# Power.net
KiCad netlist of a schematic drawn in Altium Designer
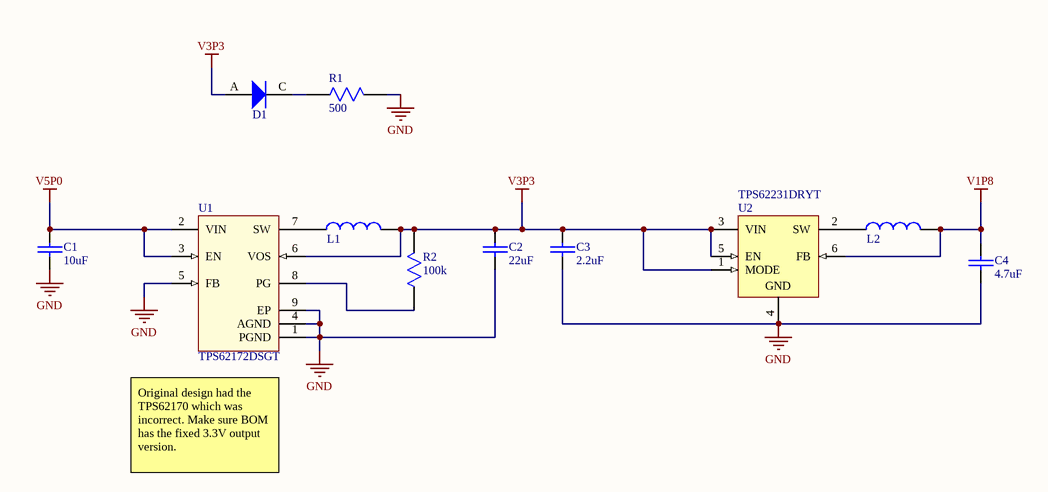
[diagram p0: Power.SchDoc]

(export (version "E")
  (design (tool "Eeschema 10.0.6"))
  (components
    (comp (ref "C1")
      (value "10uF")
      (footprint "SMD Capacitor 0603")
      (libsource (lib "DA_Component_Library") (part "Capacitor"))
    )
    (comp (ref "C2")
      (value "22uF")
      (footprint "SMD Capacitor 0603")
      (libsource (lib "DA_Component_Library") (part "Capacitor"))
    )
    (comp (ref "C3")
      (value "2.2uF")
      (footprint "SMD CAP 0402")
      (libsource (lib "DA_Component_Library") (part "Capacitor"))
    )
    (comp (ref "C4")
      (value "4.7uF")
      (footprint "SMD CAP 0402")
      (libsource (lib "DA_Component_Library") (part "Capacitor"))
    )
    (comp (ref "D1")
      (value "LED 0603")
      (footprint "LED_0603")
      (description "LTST_C195TBJRKT")
      (libsource (lib "DA_Component_Library") (part "LED 0603"))
    )
    (comp (ref "L1")
      (value "Ferrite Bead")
      (footprint "LQM21PN2R2MC0D")
      (libsource (lib "DA_Component_Library") (part "Ferrite Bead"))
    )
    (comp (ref "L2")
      (value "Ferrite Bead")
      (footprint "LQM21PN2R2MC0D")
      (libsource (lib "DA_Component_Library") (part "Ferrite Bead"))
    )
    (comp (ref "R1")
      (value "500")
      (footprint "SMD RES 0402")
      (libsource (lib "DA_Component_Library") (part "Resistor"))
    )
    (comp (ref "R2")
      (value "100k")
      (footprint "SMD RES 0402")
      (libsource (lib "DA_Component_Library") (part "Resistor"))
    )
    (comp (ref "U1")
      (value "TPS62172DSGT")
      (footprint "DSG8-1600X900TP")
      (fields (field (name "MANUFACTURER") "Texas Instruments") (field (name "PARTNUMBER") "TPS62170DSGT"))
      (libsource (lib "TI Power Management Step-Down Regulator") (part "TPS62170DSGT"))
    )
    (comp (ref "U2")
      (value "TPS62231DRYT")
      (footprint "DRY6")
      (fields (field (name "MANUFACTURER") "Texas Instruments"))
      (libsource (lib "TI Power Management Step-Down Regulator") (part "TPS62231DRYT"))
    )
  )
  (nets
    (net (code "1") (name "GND") (class "Default")
      (node (ref "C1") (pin "1") (pinfunction "1_1") (pintype "passive"))
      (node (ref "C2") (pin "1") (pinfunction "1_1") (pintype "passive"))
      (node (ref "C3") (pin "1") (pinfunction "1_1") (pintype "passive"))
      (node (ref "C4") (pin "1") (pinfunction "1_1") (pintype "passive"))
      (node (ref "R1") (pin "1") (pinfunction "1_1") (pintype "passive"))
      (node (ref "U1") (pin "1") (pinfunction "PGND_1") (pintype "power_in"))
      (node (ref "U1") (pin "4") (pinfunction "AGND_4") (pintype "power_in"))
      (node (ref "U1") (pin "5") (pinfunction "FB_5") (pintype "input"))
      (node (ref "U1") (pin "9") (pinfunction "EP_9") (pintype "power_in"))
      (node (ref "U2") (pin "4") (pinfunction "GND_4") (pintype "power_in"))
    )
    (net (code "2") (name "Net-(D1-PadC)") (class "Default")
      (node (ref "D1") (pin "C") (pinfunction "C_C") (pintype "passive"))
      (node (ref "R1") (pin "0") (pinfunction "0_0") (pintype "passive"))
    )
    (net (code "3") (name "Net-(U1-PG)") (class "Default")
      (node (ref "R2") (pin "0") (pinfunction "0_0") (pintype "passive"))
      (node (ref "U1") (pin "8") (pinfunction "PG_8") (pintype "tri_state"))
    )
    (net (code "4") (name "Net-(U1-SW)") (class "Default")
      (node (ref "L1") (pin "1") (pinfunction "1_1") (pintype "passive"))
      (node (ref "U1") (pin "7") (pinfunction "SW_7") (pintype "power_in"))
    )
    (net (code "5") (name "Net-(U2-SW)") (class "Default")
      (node (ref "L2") (pin "1") (pinfunction "1_1") (pintype "passive"))
      (node (ref "U2") (pin "2") (pinfunction "SW_2") (pintype "power_in"))
    )
    (net (code "6") (name "V1P8") (class "Default")
      (node (ref "C4") (pin "0") (pinfunction "0_0") (pintype "passive"))
      (node (ref "L2") (pin "2") (pinfunction "2_2") (pintype "passive"))
      (node (ref "U2") (pin "6") (pinfunction "FB_6") (pintype "input"))
    )
    (net (code "7") (name "V3P3") (class "Default")
      (node (ref "C2") (pin "0") (pinfunction "0_0") (pintype "passive"))
      (node (ref "C3") (pin "0") (pinfunction "0_0") (pintype "passive"))
      (node (ref "D1") (pin "A") (pinfunction "A_A") (pintype "passive"))
      (node (ref "L1") (pin "2") (pinfunction "2_2") (pintype "passive"))
      (node (ref "R2") (pin "1") (pinfunction "1_1") (pintype "passive"))
      (node (ref "U1") (pin "6") (pinfunction "VOS_6") (pintype "input"))
      (node (ref "U2") (pin "1") (pinfunction "MODE_1") (pintype "input"))
      (node (ref "U2") (pin "3") (pinfunction "VIN_3") (pintype "power_in"))
      (node (ref "U2") (pin "5") (pinfunction "EN_5") (pintype "input"))
    )
    (net (code "8") (name "V5P0") (class "Default")
      (node (ref "C1") (pin "0") (pinfunction "0_0") (pintype "passive"))
      (node (ref "U1") (pin "2") (pinfunction "VIN_2") (pintype "power_in"))
      (node (ref "U1") (pin "3") (pinfunction "EN_3") (pintype "input"))
    )
  )
)
